# Voice_Interaction_Hat_for_MakePython_v2_.net
KiCad netlist of a schematic drawn in EAGLE
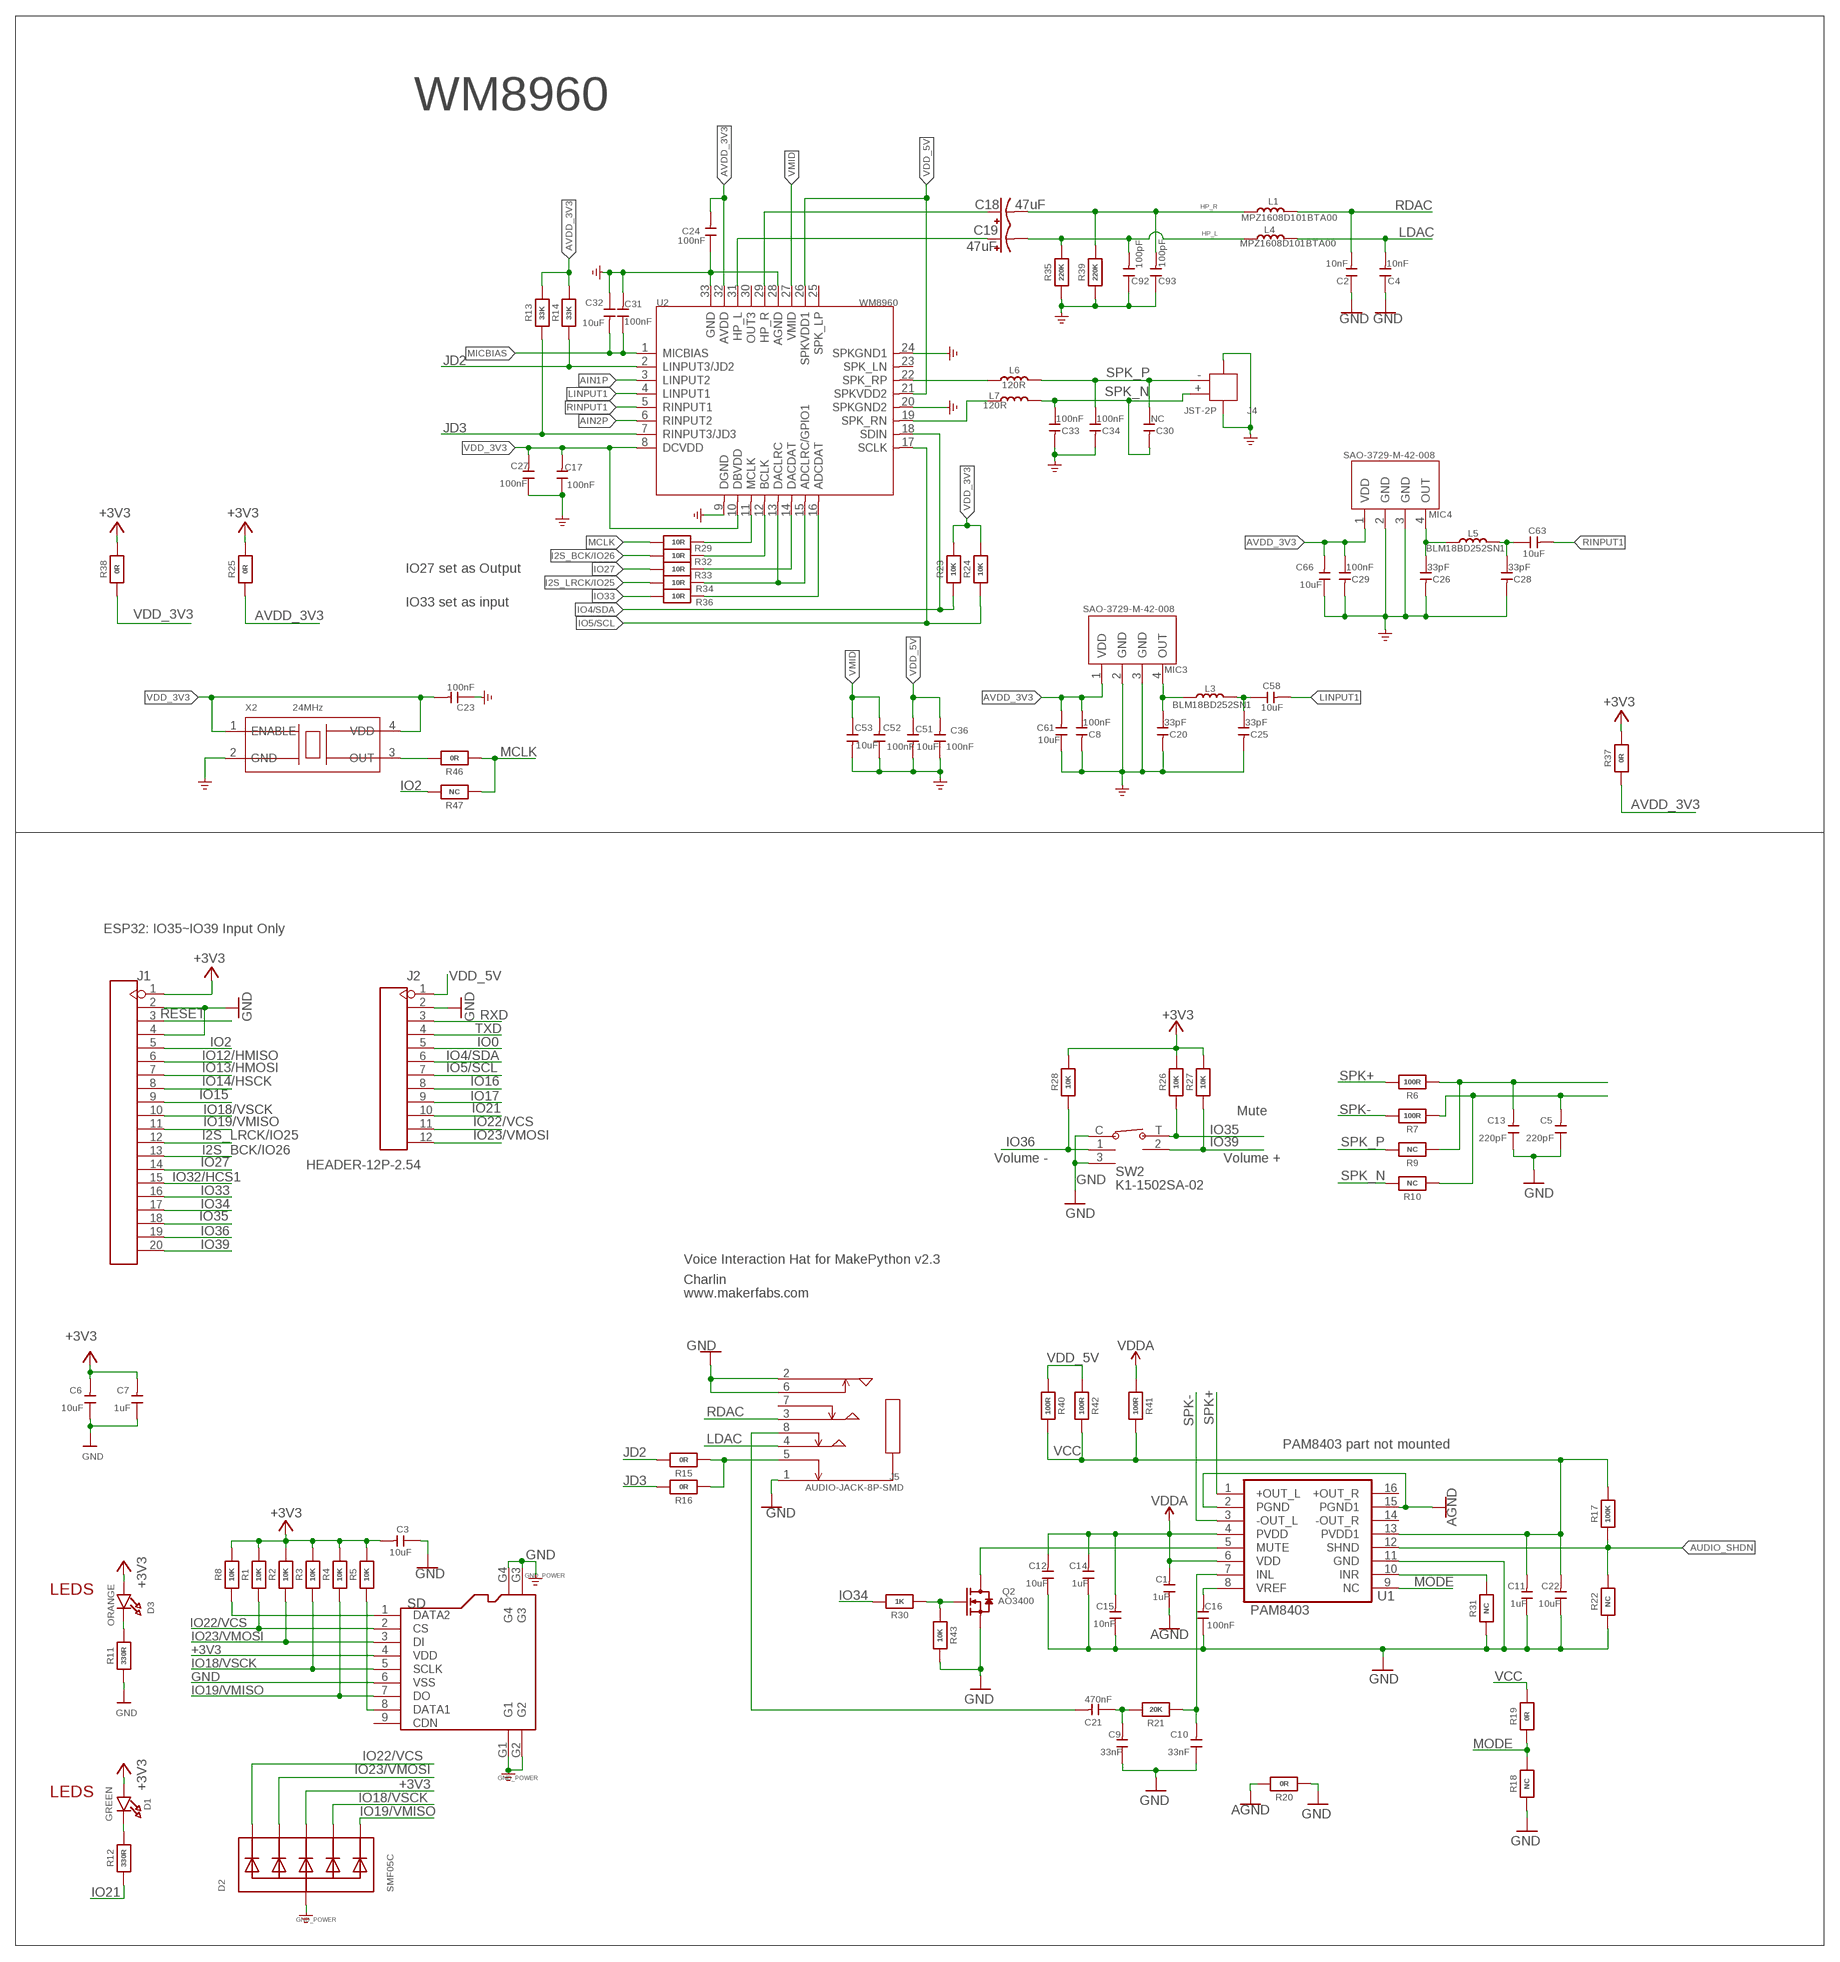
[diagram p0: schematic, sheet 1]

(export (version "E")
  (design (tool "Eeschema 10.0.6"))
  (components
    (comp (ref "C1")
      (value "1uF")
      (footprint "eagle-import:DISCRETE_C0603")
      (libsource (lib "eagle-import") (part "DISCRETE_C-0603"))
    )
    (comp (ref "C2")
      (value "10nF")
      (footprint "eagle-import:C0402")
      (libsource (lib "eagle-import") (part "CAP-0402"))
    )
    (comp (ref "C3")
      (value "10uF")
      (footprint "eagle-import:DISCRETE_C0603")
      (libsource (lib "eagle-import") (part "DISCRETE_C-0603"))
    )
    (comp (ref "C4")
      (value "10nF")
      (footprint "eagle-import:C0402")
      (libsource (lib "eagle-import") (part "CAP-0402"))
    )
    (comp (ref "C5")
      (value "220pF")
      (footprint "eagle-import:DISCRETE_C0603")
      (libsource (lib "eagle-import") (part "DISCRETE_C-0603"))
    )
    (comp (ref "C6")
      (value "10uF")
      (footprint "eagle-import:DISCRETE_C0603")
      (libsource (lib "eagle-import") (part "DISCRETE_C-0603"))
    )
    (comp (ref "C7")
      (value "1uF")
      (footprint "eagle-import:DISCRETE_C0603")
      (libsource (lib "eagle-import") (part "DISCRETE_C-0603"))
    )
    (comp (ref "C8")
      (value "100nF")
      (footprint "eagle-import:C0603")
      (libsource (lib "eagle-import") (part "CAP-0603"))
    )
    (comp (ref "C9")
      (value "33nF")
      (footprint "eagle-import:DISCRETE_C0603")
      (libsource (lib "eagle-import") (part "DISCRETE_C-0603"))
    )
    (comp (ref "C10")
      (value "33nF")
      (footprint "eagle-import:DISCRETE_C0603")
      (libsource (lib "eagle-import") (part "DISCRETE_C-0603"))
    )
    (comp (ref "C11")
      (value "1uF")
      (footprint "eagle-import:DISCRETE_C0603")
      (libsource (lib "eagle-import") (part "DISCRETE_C-0603"))
    )
    (comp (ref "C12")
      (value "10uF")
      (footprint "eagle-import:DISCRETE_C0603")
      (libsource (lib "eagle-import") (part "DISCRETE_C-0603"))
    )
    (comp (ref "C13")
      (value "220pF")
      (footprint "eagle-import:DISCRETE_C0603")
      (libsource (lib "eagle-import") (part "DISCRETE_C-0603"))
    )
    (comp (ref "C14")
      (value "1uF")
      (footprint "eagle-import:DISCRETE_C0603")
      (libsource (lib "eagle-import") (part "DISCRETE_C-0603"))
    )
    (comp (ref "C15")
      (value "10nF")
      (footprint "eagle-import:DISCRETE_C0603")
      (libsource (lib "eagle-import") (part "DISCRETE_C-0603"))
    )
    (comp (ref "C16")
      (value "100nF")
      (footprint "eagle-import:DISCRETE_C0603")
      (libsource (lib "eagle-import") (part "DISCRETE_C-0603"))
    )
    (comp (ref "C17")
      (value "100nF")
      (footprint "eagle-import:C0402")
      (libsource (lib "eagle-import") (part "CAP-0402"))
    )
    (comp (ref "C18")
      (value "47uF")
      (footprint "eagle-import:EIA3528")
      (libsource (lib "eagle-import") (part "47UF-POLAR-EIA3528-10V-10%"))
    )
    (comp (ref "C19")
      (value "47uF")
      (footprint "eagle-import:EIA3528")
      (libsource (lib "eagle-import") (part "47UF-POLAR-EIA3528-10V-10%"))
    )
    (comp (ref "C20")
      (value "33pF")
      (footprint "eagle-import:C0603")
      (libsource (lib "eagle-import") (part "CAP-0603"))
    )
    (comp (ref "C21")
      (value "470nF")
      (footprint "eagle-import:DISCRETE_C0603")
      (libsource (lib "eagle-import") (part "DISCRETE_C-0603"))
    )
    (comp (ref "C22")
      (value "10uF")
      (footprint "eagle-import:DISCRETE_C0603")
      (libsource (lib "eagle-import") (part "DISCRETE_C-0603"))
    )
    (comp (ref "C23")
      (value "100nF")
      (footprint "eagle-import:C0402")
      (libsource (lib "eagle-import") (part "CAP-0402"))
    )
    (comp (ref "C24")
      (value "100nF")
      (footprint "eagle-import:C0402")
      (libsource (lib "eagle-import") (part "CAP-0402"))
    )
    (comp (ref "C25")
      (value "33pF")
      (footprint "eagle-import:C0603")
      (libsource (lib "eagle-import") (part "CAP-0603"))
    )
    (comp (ref "C26")
      (value "33pF")
      (footprint "eagle-import:C0603")
      (libsource (lib "eagle-import") (part "CAP-0603"))
    )
    (comp (ref "C27")
      (value "100nF")
      (footprint "eagle-import:C0402")
      (libsource (lib "eagle-import") (part "CAP-0402"))
    )
    (comp (ref "C28")
      (value "33pF")
      (footprint "eagle-import:C0603")
      (libsource (lib "eagle-import") (part "CAP-0603"))
    )
    (comp (ref "C29")
      (value "100nF")
      (footprint "eagle-import:C0603")
      (libsource (lib "eagle-import") (part "CAP-0603"))
    )
    (comp (ref "C30")
      (value "NC")
      (footprint "eagle-import:C0603")
      (libsource (lib "eagle-import") (part "CAP-0603"))
    )
    (comp (ref "C31")
      (value "100nF")
      (footprint "eagle-import:C0402")
      (libsource (lib "eagle-import") (part "CAP-0402"))
    )
    (comp (ref "C32")
      (value "10uF")
      (footprint "eagle-import:C0603")
      (libsource (lib "eagle-import") (part "CAP-0603"))
    )
    (comp (ref "C33")
      (value "100nF")
      (footprint "eagle-import:C0603")
      (libsource (lib "eagle-import") (part "CAP-0603"))
    )
    (comp (ref "C34")
      (value "100nF")
      (footprint "eagle-import:C0603")
      (libsource (lib "eagle-import") (part "CAP-0603"))
    )
    (comp (ref "C36")
      (value "100nF")
      (footprint "eagle-import:C0402")
      (libsource (lib "eagle-import") (part "CAP-0402"))
    )
    (comp (ref "C51")
      (value "10uF")
      (footprint "eagle-import:C0603")
      (libsource (lib "eagle-import") (part "CAP-0603"))
    )
    (comp (ref "C52")
      (value "100nF")
      (footprint "eagle-import:C0402")
      (libsource (lib "eagle-import") (part "CAP-0402"))
    )
    (comp (ref "C53")
      (value "10uF")
      (footprint "eagle-import:C0603")
      (libsource (lib "eagle-import") (part "CAP-0603"))
    )
    (comp (ref "C58")
      (value "10uF")
      (footprint "eagle-import:C0603")
      (libsource (lib "eagle-import") (part "CAP-0603"))
    )
    (comp (ref "C61")
      (value "10uF")
      (footprint "eagle-import:C0603")
      (libsource (lib "eagle-import") (part "CAP-0603"))
    )
    (comp (ref "C63")
      (value "10uF")
      (footprint "eagle-import:C0603")
      (libsource (lib "eagle-import") (part "CAP-0603"))
    )
    (comp (ref "C66")
      (value "10uF")
      (footprint "eagle-import:C0603")
      (libsource (lib "eagle-import") (part "CAP-0603"))
    )
    (comp (ref "C92")
      (value "100pF")
      (footprint "eagle-import:C0402")
      (libsource (lib "eagle-import") (part "CAP-0402"))
    )
    (comp (ref "C93")
      (value "100pF")
      (footprint "eagle-import:C0402")
      (libsource (lib "eagle-import") (part "CAP-0402"))
    )
    (comp (ref "D1")
      (value "GREEN")
      (footprint "eagle-import:CHIPLED_0805_NOOUTLINE")
      (libsource (lib "eagle-import") (part "LED0805_NOOUTLINE"))
    )
    (comp (ref "D2")
      (value "SMF05C")
      (footprint "eagle-import:SOT363")
      (libsource (lib "eagle-import") (part "TVSARRAY_5LANE"))
    )
    (comp (ref "D3")
      (value "ORANGE")
      (footprint "eagle-import:CHIPLED_0805_NOOUTLINE")
      (libsource (lib "eagle-import") (part "LED0805_NOOUTLINE"))
    )
    (comp (ref "J1")
      (value "HEADER-20P-2.54")
      (footprint "eagle-import:20P-2.54")
      (libsource (lib "eagle-import") (part "HEADER-20P-2.54"))
    )
    (comp (ref "J2")
      (value "HEADER-12P-2.54")
      (footprint "eagle-import:12P-2.54")
      (libsource (lib "eagle-import") (part "HEADER-12P-2.54"))
    )
    (comp (ref "J4")
      (value "JST-2P")
      (footprint "eagle-import:HW2-SMD-2.0-90D")
      (libsource (lib "eagle-import") (part "JST-2P-SMD'2.0'"))
    )
    (comp (ref "J5")
      (value "AUDIO-JACK-8P-SMD")
      (footprint "eagle-import:AUDIO8P-SMD-3.5-14.5X6.1X4.0MM")
      (libsource (lib "eagle-import") (part "AUDIO-JACK-8P-SMD'PJ-393'"))
    )
    (comp (ref "L1")
      (value "MPZ1608D101BTA00")
      (footprint "eagle-import:L0603")
      (libsource (lib "eagle-import") (part "INDUCTOR/FERRITE-BEAD'0603'"))
    )
    (comp (ref "L3")
      (value "BLM18BD252SN1")
      (footprint "eagle-import:L0603")
      (libsource (lib "eagle-import") (part "INDUCTOR/FERRITE-BEAD'0603'"))
    )
    (comp (ref "L4")
      (value "MPZ1608D101BTA00")
      (footprint "eagle-import:L0603")
      (libsource (lib "eagle-import") (part "INDUCTOR/FERRITE-BEAD'0603'"))
    )
    (comp (ref "L5")
      (value "BLM18BD252SN1")
      (footprint "eagle-import:L0603")
      (libsource (lib "eagle-import") (part "INDUCTOR/FERRITE-BEAD'0603'"))
    )
    (comp (ref "L6")
      (value "120R")
      (footprint "eagle-import:L0603")
      (libsource (lib "eagle-import") (part "INDUCTOR/FERRITE-BEAD'0603'"))
    )
    (comp (ref "L7")
      (value "120R")
      (footprint "eagle-import:L0603")
      (libsource (lib "eagle-import") (part "INDUCTOR/FERRITE-BEAD'0603'"))
    )
    (comp (ref "MIC3")
      (value "SAO-3729-M-42-008")
      (footprint "eagle-import:MIC4-SMD-3.76X2.95MM")
      (libsource (lib "eagle-import") (part "MIC-MSM421A3729H8-C"))
    )
    (comp (ref "MIC4")
      (value "SAO-3729-M-42-008")
      (footprint "eagle-import:MIC4-SMD-3.76X2.95MM")
      (libsource (lib "eagle-import") (part "MIC-MSM421A3729H8-C"))
    )
    (comp (ref "Q2")
      (value "AO3400")
      (footprint "eagle-import:SOT23@1")
      (libsource (lib "eagle-import") (part "MOSFET-N'SOT23'"))
    )
    (comp (ref "R1")
      (value "10K")
      (footprint "eagle-import:0603-NO")
      (libsource (lib "eagle-import") (part "RESISTOR_0603_NOOUT"))
    )
    (comp (ref "R2")
      (value "10K")
      (footprint "eagle-import:0603-NO")
      (libsource (lib "eagle-import") (part "RESISTOR_0603_NOOUT"))
    )
    (comp (ref "R3")
      (value "10K")
      (footprint "eagle-import:0603-NO")
      (libsource (lib "eagle-import") (part "RESISTOR_0603_NOOUT"))
    )
    (comp (ref "R4")
      (value "10K")
      (footprint "eagle-import:0603-NO")
      (libsource (lib "eagle-import") (part "RESISTOR_0603_NOOUT"))
    )
    (comp (ref "R5")
      (value "10K")
      (footprint "eagle-import:0603-NO")
      (libsource (lib "eagle-import") (part "RESISTOR_0603_NOOUT"))
    )
    (comp (ref "R6")
      (value "100R")
      (footprint "eagle-import:0603-NO")
      (libsource (lib "eagle-import") (part "RESISTOR_0603_NOOUT"))
    )
    (comp (ref "R7")
      (value "100R")
      (footprint "eagle-import:0603-NO")
      (libsource (lib "eagle-import") (part "RESISTOR_0603_NOOUT"))
    )
    (comp (ref "R8")
      (value "10K")
      (footprint "eagle-import:0603-NO")
      (libsource (lib "eagle-import") (part "RESISTOR_0603_NOOUT"))
    )
    (comp (ref "R9")
      (value "NC")
      (footprint "eagle-import:0603-NO")
      (libsource (lib "eagle-import") (part "RESISTOR_0603_NOOUT"))
    )
    (comp (ref "R10")
      (value "NC")
      (footprint "eagle-import:0603-NO")
      (libsource (lib "eagle-import") (part "RESISTOR_0603_NOOUT"))
    )
    (comp (ref "R11")
      (value "330R")
      (footprint "eagle-import:0603-NO")
      (libsource (lib "eagle-import") (part "RESISTOR_0603_NOOUT"))
    )
    (comp (ref "R12")
      (value "330R")
      (footprint "eagle-import:0603-NO")
      (libsource (lib "eagle-import") (part "RESISTOR_0603_NOOUT"))
    )
    (comp (ref "R13")
      (value "33K")
      (footprint "eagle-import:0603-NO")
      (libsource (lib "eagle-import") (part "RESISTOR_0603_NOOUT"))
    )
    (comp (ref "R14")
      (value "33K")
      (footprint "eagle-import:0603-NO")
      (libsource (lib "eagle-import") (part "RESISTOR_0603_NOOUT"))
    )
    (comp (ref "R15")
      (value "0R")
      (footprint "eagle-import:0603-NO")
      (libsource (lib "eagle-import") (part "RESISTOR_0603_NOOUT"))
    )
    (comp (ref "R16")
      (value "0R")
      (footprint "eagle-import:0603-NO")
      (libsource (lib "eagle-import") (part "RESISTOR_0603_NOOUT"))
    )
    (comp (ref "R17")
      (value "100K")
      (footprint "eagle-import:0603-NO")
      (libsource (lib "eagle-import") (part "RESISTOR_0603_NOOUT"))
    )
    (comp (ref "R18")
      (value "NC")
      (footprint "eagle-import:0603-NO")
      (libsource (lib "eagle-import") (part "RESISTOR_0603_NOOUT"))
    )
    (comp (ref "R19")
      (value "0R")
      (footprint "eagle-import:0603-NO")
      (libsource (lib "eagle-import") (part "RESISTOR_0603_NOOUT"))
    )
    (comp (ref "R20")
      (value "0R")
      (footprint "eagle-import:0603-NO")
      (libsource (lib "eagle-import") (part "RESISTOR_0603_NOOUT"))
    )
    (comp (ref "R21")
      (value "20K")
      (footprint "eagle-import:0603-NO")
      (libsource (lib "eagle-import") (part "RESISTOR_0603_NOOUT"))
    )
    (comp (ref "R22")
      (value "NC")
      (footprint "eagle-import:0603-NO")
      (libsource (lib "eagle-import") (part "RESISTOR_0603_NOOUT"))
    )
    (comp (ref "R23")
      (value "10K")
      (footprint "eagle-import:0603-NO")
      (libsource (lib "eagle-import") (part "RESISTOR_0603_NOOUT"))
    )
    (comp (ref "R24")
      (value "10K")
      (footprint "eagle-import:0603-NO")
      (libsource (lib "eagle-import") (part "RESISTOR_0603_NOOUT"))
    )
    (comp (ref "R25")
      (value "0R")
      (footprint "eagle-import:0603-NO")
      (libsource (lib "eagle-import") (part "RESISTOR_0603_NOOUT"))
    )
    (comp (ref "R26")
      (value "10K")
      (footprint "eagle-import:0603-NO")
      (libsource (lib "eagle-import") (part "RESISTOR_0603_NOOUT"))
    )
    (comp (ref "R27")
      (value "10K")
      (footprint "eagle-import:0603-NO")
      (libsource (lib "eagle-import") (part "RESISTOR_0603_NOOUT"))
    )
    (comp (ref "R28")
      (value "10K")
      (footprint "eagle-import:0603-NO")
      (libsource (lib "eagle-import") (part "RESISTOR_0603_NOOUT"))
    )
    (comp (ref "R29")
      (value "10R")
      (footprint "eagle-import:0603-NO")
      (libsource (lib "eagle-import") (part "RESISTOR_0603_NOOUT"))
    )
    (comp (ref "R30")
      (value "1K")
      (footprint "eagle-import:0603-NO")
      (libsource (lib "eagle-import") (part "RESISTOR_0603_NOOUT"))
    )
    (comp (ref "R31")
      (value "NC")
      (footprint "eagle-import:0603-NO")
      (libsource (lib "eagle-import") (part "RESISTOR_0603_NOOUT"))
    )
    (comp (ref "R32")
      (value "10R")
      (footprint "eagle-import:0603-NO")
      (libsource (lib "eagle-import") (part "RESISTOR_0603_NOOUT"))
    )
    (comp (ref "R33")
      (value "10R")
      (footprint "eagle-import:0603-NO")
      (libsource (lib "eagle-import") (part "RESISTOR_0603_NOOUT"))
    )
    (comp (ref "R34")
      (value "10R")
      (footprint "eagle-import:0603-NO")
      (libsource (lib "eagle-import") (part "RESISTOR_0603_NOOUT"))
    )
    (comp (ref "R35")
      (value "220K")
      (footprint "eagle-import:0603-NO")
      (libsource (lib "eagle-import") (part "RESISTOR_0603_NOOUT"))
    )
    (comp (ref "R36")
      (value "10R")
      (footprint "eagle-import:0603-NO")
      (libsource (lib "eagle-import") (part "RESISTOR_0603_NOOUT"))
    )
    (comp (ref "R37")
      (value "0R")
      (footprint "eagle-import:0603-NO")
      (libsource (lib "eagle-import") (part "RESISTOR_0603_NOOUT"))
    )
    (comp (ref "R38")
      (value "0R")
      (footprint "eagle-import:0603-NO")
      (libsource (lib "eagle-import") (part "RESISTOR_0603_NOOUT"))
    )
    (comp (ref "R39")
      (value "220K")
      (footprint "eagle-import:0603-NO")
      (libsource (lib "eagle-import") (part "RESISTOR_0603_NOOUT"))
    )
    (comp (ref "R40")
      (value "100R")
      (footprint "eagle-import:0603-NO")
      (libsource (lib "eagle-import") (part "RESISTOR_0603_NOOUT"))
    )
    (comp (ref "R41")
      (value "100R")
      (footprint "eagle-import:0603-NO")
      (libsource (lib "eagle-import") (part "RESISTOR_0603_NOOUT"))
    )
    (comp (ref "R42")
      (value "100R")
      (footprint "eagle-import:0603-NO")
      (libsource (lib "eagle-import") (part "RESISTOR_0603_NOOUT"))
    )
    (comp (ref "R43")
      (value "10K")
      (footprint "eagle-import:0603-NO")
      (libsource (lib "eagle-import") (part "RESISTOR_0603_NOOUT"))
    )
    (comp (ref "R46")
      (value "0R")
      (footprint "eagle-import:0603-NO")
      (libsource (lib "eagle-import") (part "RESISTOR_0603_NOOUT"))
    )
    (comp (ref "R47")
      (value "NC")
      (footprint "eagle-import:0603-NO")
      (libsource (lib "eagle-import") (part "RESISTOR_0603_NOOUT"))
    )
    (comp (ref "SD")
      (value "HOLDER-MICROSD-9P")
      (footprint "eagle-import:9P-SMD-W_-RING")
      (libsource (lib "eagle-import") (part "HOLDER-MICROSD-9P"))
    )
    (comp (ref "SW2")
      (value "K1-1502SA-02")
      (footprint "eagle-import:SMD5-60P-1180L1170W")
      (libsource (lib "eagle-import") (part "K1-1502SA-02"))
    )
    (comp (ref "U1")
      (value "PAM8403")
      (footprint "eagle-import:SOP-16")
      (libsource (lib "eagle-import") (part "PAM8403"))
    )
    (comp (ref "U2")
      (value "WM8960")
      (footprint "eagle-import:QFN32G-0.5-5X5MM")
      (libsource (lib "eagle-import") (part "AMPLIFIER-WM8960"))
    )
    (comp (ref "X2")
      (value "24MHz")
      (footprint "eagle-import:OSC4-SMD-2.5X2.0X0.8MM")
      (libsource (lib "eagle-import") (part "CRYSTAL-OSCILLATOR2.52.0"))
    )
  )
  (nets
    (net (code "1") (name "+3V3") (class "Default")
      (node (ref "C3") (pin "2") (pinfunction "2_2") (pintype "passive"))
      (node (ref "C6") (pin "2") (pinfunction "2_2") (pintype "passive"))
      (node (ref "C7") (pin "2") (pinfunction "2_2") (pintype "passive"))
      (node (ref "D1") (pin "A") (pinfunction "A_A") (pintype "passive"))
      (node (ref "D2") (pin "4") (pinfunction "C3_4") (pintype "passive"))
      (node (ref "D3") (pin "A") (pinfunction "A_A") (pintype "passive"))
      (node (ref "J1") (pin "1") (pinfunction "P$1_1") (pintype "bidirectional"))
      (node (ref "R1") (pin "2") (pinfunction "2_2") (pintype "passive"))
      (node (ref "R2") (pin "2") (pinfunction "2_2") (pintype "passive"))
      (node (ref "R25") (pin "2") (pinfunction "2_2") (pintype "passive"))
      (node (ref "R26") (pin "2") (pinfunction "2_2") (pintype "passive"))
      (node (ref "R27") (pin "2") (pinfunction "2_2") (pintype "passive"))
      (node (ref "R28") (pin "2") (pinfunction "2_2") (pintype "passive"))
      (node (ref "R3") (pin "2") (pinfunction "2_2") (pintype "passive"))
      (node (ref "R37") (pin "2") (pinfunction "2_2") (pintype "passive"))
      (node (ref "R38") (pin "2") (pinfunction "2_2") (pintype "passive"))
      (node (ref "R4") (pin "2") (pinfunction "2_2") (pintype "passive"))
      (node (ref "R5") (pin "2") (pinfunction "2_2") (pintype "passive"))
      (node (ref "R8") (pin "2") (pinfunction "2_2") (pintype "passive"))
      (node (ref "SD") (pin "4") (pinfunction "VDD_4") (pintype "bidirectional"))
    )
    (net (code "2") (name "/HP_L") (class "Default")
      (node (ref "C19") (pin "C") (pinfunction "-_C") (pintype "passive"))
      (node (ref "C92") (pin "2") (pinfunction "2_2") (pintype "passive"))
      (node (ref "L4") (pin "1") (pinfunction "1_1") (pintype "passive"))
      (node (ref "R35") (pin "2") (pinfunction "2_2") (pintype "passive"))
    )
    (net (code "3") (name "/HP_R") (class "Default")
      (node (ref "C18") (pin "C") (pinfunction "-_C") (pintype "passive"))
      (node (ref "C93") (pin "2") (pinfunction "2_2") (pintype "passive"))
      (node (ref "L1") (pin "1") (pinfunction "1_1") (pintype "passive"))
      (node (ref "R39") (pin "2") (pinfunction "2_2") (pintype "passive"))
    )
    (net (code "4") (name "/IO0") (class "Default")
      (node (ref "J2") (pin "5") (pinfunction "5_5") (pintype "bidirectional"))
    )
    (net (code "5") (name "/IO2") (class "Default")
      (node (ref "J1") (pin "5") (pinfunction "P$5_5") (pintype "bidirectional"))
      (node (ref "R47") (pin "2") (pinfunction "2_2") (pintype "passive"))
    )
    (net (code "6") (name "/IO12{slash}HMISO") (class "Default")
      (node (ref "J1") (pin "6") (pinfunction "P$6_6") (pintype "bidirectional"))
    )
    (net (code "7") (name "/IO13{slash}HMOSI") (class "Default")
      (node (ref "J1") (pin "7") (pinfunction "P$7_7") (pintype "bidirectional"))
    )
    (net (code "8") (name "/IO14{slash}HSCK") (class "Default")
      (node (ref "J1") (pin "8") (pinfunction "P$8_8") (pintype "bidirectional"))
    )
    (net (code "9") (name "/IO15") (class "Default")
      (node (ref "J1") (pin "9") (pinfunction "P$9_9") (pintype "bidirectional"))
    )
    (net (code "10") (name "/IO16") (class "Default")
      (node (ref "J2") (pin "8") (pinfunction "8_8") (pintype "bidirectional"))
    )
    (net (code "11") (name "/IO17") (class "Default")
      (node (ref "J2") (pin "9") (pinfunction "9_9") (pintype "bidirectional"))
    )
    (net (code "12") (name "/IO18{slash}VSCK") (class "Default")
      (node (ref "D2") (pin "5") (pinfunction "C4_5") (pintype "passive"))
      (node (ref "J1") (pin "10") (pinfunction "P$10_10") (pintype "bidirectional"))
      (node (ref "R3") (pin "1") (pinfunction "1_1") (pintype "passive"))
      (node (ref "SD") (pin "5") (pinfunction "SCLK_5") (pintype "bidirectional"))
    )
    (net (code "13") (name "/IO19{slash}VMISO") (class "Default")
      (node (ref "D2") (pin "6") (pinfunction "C5_6") (pintype "passive"))
      (node (ref "J1") (pin "11") (pinfunction "P$11_11") (pintype "bidirectional"))
      (node (ref "R4") (pin "1") (pinfunction "1_1") (pintype "passive"))
      (node (ref "SD") (pin "7") (pinfunction "DO_7") (pintype "bidirectional"))
    )
    (net (code "14") (name "/IO21") (class "Default")
      (node (ref "J2") (pin "10") (pinfunction "10_10") (pintype "bidirectional"))
      (node (ref "R12") (pin "1") (pinfunction "1_1") (pintype "passive"))
    )
    (net (code "15") (name "/IO22{slash}VCS") (class "Default")
      (node (ref "D2") (pin "1") (pinfunction "C1_1") (pintype "passive"))
      (node (ref "J2") (pin "11") (pinfunction "11_11") (pintype "bidirectional"))
      (node (ref "R1") (pin "1") (pinfunction "1_1") (pintype "passive"))
      (node (ref "SD") (pin "2") (pinfunction "CS_2") (pintype "bidirectional"))
    )
    (net (code "16") (name "/IO23{slash}VMOSI") (class "Default")
      (node (ref "D2") (pin "3") (pinfunction "C2_3") (pintype "passive"))
      (node (ref "J2") (pin "12") (pinfunction "12_12") (pintype "bidirectional"))
      (node (ref "R2") (pin "1") (pinfunction "1_1") (pintype "passive"))
      (node (ref "SD") (pin "3") (pinfunction "DI_3") (pintype "bidirectional"))
    )
    (net (code "17") (name "/IO32{slash}HCS1") (class "Default")
      (node (ref "J1") (pin "15") (pinfunction "P$15_15") (pintype "bidirectional"))
    )
    (net (code "18") (name "/IO34") (class "Default")
      (node (ref "J1") (pin "17") (pinfunction "P$17_17") (pintype "bidirectional"))
      (node (ref "R30") (pin "2") (pinfunction "2_2") (pintype "passive"))
    )
    (net (code "19") (name "/IO35") (class "Default")
      (node (ref "J1") (pin "18") (pinfunction "P$18_18") (pintype "bidirectional"))
      (node (ref "R26") (pin "1") (pinfunction "1_1") (pintype "passive"))
      (node (ref "SW2") (pin "T") (pinfunction "T_T") (pintype "bidirectional"))
    )
    (net (code "20") (name "/IO36") (class "Default")
      (node (ref "J1") (pin "19") (pinfunction "P$19_19") (pintype "bidirectional"))
      (node (ref "R28") (pin "1") (pinfunction "1_1") (pintype "passive"))
      (node (ref "SW2") (pin "1") (pinfunction "1_1") (pintype "bidirectional"))
    )
    (net (code "21") (name "/IO39") (class "Default")
      (node (ref "J1") (pin "20") (pinfunction "P$20_20") (pintype "bidirectional"))
      (node (ref "R27") (pin "1") (pinfunction "1_1") (pintype "passive"))
      (node (ref "SW2") (pin "2") (pinfunction "2_2") (pintype "bidirectional"))
    )
    (net (code "22") (name "/JD2") (class "Default")
      (node (ref "R14") (pin "1") (pinfunction "1_1") (pintype "passive"))
      (node (ref "R15") (pin "2") (pinfunction "2_2") (pintype "passive"))
      (node (ref "U2") (pin "2") (pinfunction "LINPUT3/JD2_2") (pintype "bidirectional"))
    )
    (net (code "23") (name "/JD3") (class "Default")
      (node (ref "R13") (pin "1") (pinfunction "1_1") (pintype "passive"))
      (node (ref "R16") (pin "2") (pinfunction "2_2") (pintype "passive"))
      (node (ref "U2") (pin "7") (pinfunction "RINPUT3/JD3_7") (pintype "bidirectional"))
    )
    (net (code "24") (name "/LDAC") (class "Default")
      (node (ref "C4") (pin "2") (pinfunction "2_2") (pintype "passive"))
      (node (ref "J5") (pin "4") (pinfunction "4_4") (pintype "bidirectional"))
      (node (ref "L4") (pin "2") (pinfunction "2_2") (pintype "passive"))
    )
    (net (code "25") (name "/MODE") (class "Default")
      (node (ref "R18") (pin "2") (pinfunction "2_2") (pintype "passive"))
      (node (ref "R19") (pin "1") (pinfunction "1_1") (pintype "passive"))
      (node (ref "U1") (pin "9") (pinfunction "NC_9") (pintype "output"))
    )
    (net (code "26") (name "/RDAC") (class "Default")
      (node (ref "C2") (pin "2") (pinfunction "2_2") (pintype "passive"))
      (node (ref "J5") (pin "3") (pinfunction "3_3") (pintype "bidirectional"))
      (node (ref "L1") (pin "2") (pinfunction "2_2") (pintype "passive"))
    )
    (net (code "27") (name "/RESET") (class "Default")
      (node (ref "J1") (pin "3") (pinfunction "P$3_3") (pintype "bidirectional"))
    )
    (net (code "28") (name "/RXD") (class "Default")
      (node (ref "J2") (pin "3") (pinfunction "3_3") (pintype "bidirectional"))
    )
    (net (code "29") (name "/SPK+") (class "Default")
      (node (ref "R6") (pin "2") (pinfunction "2_2") (pintype "passive"))
      (node (ref "U1") (pin "1") (pinfunction "+OUT_L_1") (pintype "input"))
    )
    (net (code "30") (name "/SPK-") (class "Default")
      (node (ref "R7") (pin "2") (pinfunction "2_2") (pintype "passive"))
      (node (ref "U1") (pin "3") (pinfunction "-OUT_L_3") (pintype "input"))
    )
    (net (code "31") (name "/SPK_N") (class "Default")
      (node (ref "C30") (pin "2") (pinfunction "2_2") (pintype "passive"))
      (node (ref "C33") (pin "1") (pinfunction "1_1") (pintype "passive"))
      (node (ref "J4") (pin "+") (pinfunction "1_+") (pintype "bidirectional"))
      (node (ref "L7") (pin "2") (pinfunction "2_2") (pintype "passive"))
      (node (ref "R10") (pin "2") (pinfunction "2_2") (pintype "passive"))
    )
    (net (code "32") (name "/SPK_P") (class "Default")
      (node (ref "C30") (pin "1") (pinfunction "1_1") (pintype "passive"))
      (node (ref "C34") (pin "1") (pinfunction "1_1") (pintype "passive"))
      (node (ref "J4") (pin "-") (pinfunction "2_-") (pintype "bidirectional"))
      (node (ref "L6") (pin "2") (pinfunction "2_2") (pintype "passive"))
      (node (ref "R9") (pin "2") (pinfunction "2_2") (pintype "passive"))
    )
    (net (code "33") (name "/TXD") (class "Default")
      (node (ref "J2") (pin "4") (pinfunction "4_4") (pintype "bidirectional"))
    )
    (net (code "34") (name "/VCC") (class "Default")
      (node (ref "C11") (pin "2") (pinfunction "2_2") (pintype "passive"))
      (node (ref "C22") (pin "2") (pinfunction "2_2") (pintype "passive"))
      (node (ref "R17") (pin "2") (pinfunction "2_2") (pintype "passive"))
      (node (ref "R19") (pin "2") (pinfunction "2_2") (pintype "passive"))
      (node (ref "R40") (pin "2") (pinfunction "2_2") (pintype "passive"))
      (node (ref "R41") (pin "2") (pinfunction "2_2") (pintype "passive"))
      (node (ref "R42") (pin "2") (pinfunction "2_2") (pintype "passive"))
      (node (ref "U1") (pin "13") (pinfunction "PVDD1_13") (pintype "output"))
    )
    (net (code "35") (name "AGND") (class "Default")
      (node (ref "C1") (pin "1") (pinfunction "1_1") (pintype "passive"))
      (node (ref "R20") (pin "2") (pinfunction "2_2") (pintype "passive"))
      (node (ref "U1") (pin "15") (pinfunction "PGND1_15") (pintype "output"))
      (node (ref "U1") (pin "2") (pinfunction "PGND_2") (pintype "input"))
    )
    (net (code "36") (name "AIN1P") (class "Default")
      (node (ref "U2") (pin "3") (pinfunction "LINPUT2_3") (pintype "bidirectional"))
    )
    (net (code "37") (name "AIN2P") (class "Default")
      (node (ref "U2") (pin "6") (pinfunction "RINPUT2_6") (pintype "bidirectional"))
    )
    (net (code "38") (name "AUDIO_SHDN") (class "Default")
      (node (ref "R17") (pin "1") (pinfunction "1_1") (pintype "passive"))
      (node (ref "R22") (pin "2") (pinfunction "2_2") (pintype "passive"))
      (node (ref "U1") (pin "12") (pinfunction "SHND_12") (pintype "output"))
    )
    (net (code "39") (name "AVDD_3V3") (class "Default")
      (node (ref "C24") (pin "2") (pinfunction "2_2") (pintype "passive"))
      (node (ref "C29") (pin "1") (pinfunction "1_1") (pintype "passive"))
      (node (ref "C61") (pin "2") (pinfunction "2_2") (pintype "passive"))
      (node (ref "C66") (pin "2") (pinfunction "2_2") (pintype "passive"))
      (node (ref "C8") (pin "1") (pinfunction "1_1") (pintype "passive"))
      (node (ref "MIC3") (pin "1") (pinfunction "VDD_1") (pintype "bidirectional"))
      (node (ref "MIC4") (pin "1") (pinfunction "VDD_1") (pintype "bidirectional"))
      (node (ref "R13") (pin "2") (pinfunction "2_2") (pintype "passive"))
      (node (ref "R14") (pin "2") (pinfunction "2_2") (pintype "passive"))
      (node (ref "R25") (pin "1") (pinfunction "1_1") (pintype "passive"))
      (node (ref "R37") (pin "1") (pinfunction "1_1") (pintype "passive"))
      (node (ref "U2") (pin "32") (pinfunction "AVDD_32") (pintype "bidirectional"))
    )
    (net (code "40") (name "GND") (class "Default")
      (node (ref "C10") (pin "1") (pinfunction "1_1") (pintype "passive"))
      (node (ref "C11") (pin "1") (pinfunction "1_1") (pintype "passive"))
      (node (ref "C12") (pin "1") (pinfunction "1_1") (pintype "passive"))
      (node (ref "C13") (pin "1") (pinfunction "1_1") (pintype "passive"))
      (node (ref "C14") (pin "1") (pinfunction "1_1") (pintype "passive"))
      (node (ref "C15") (pin "1") (pinfunction "1_1") (pintype "passive"))
      (node (ref "C16") (pin "1") (pinfunction "1_1") (pintype "passive"))
      (node (ref "C17") (pin "1") (pinfunction "1_1") (pintype "passive"))
      (node (ref "C2") (pin "1") (pinfunction "1_1") (pintype "passive"))
      (node (ref "C20") (pin "2") (pinfunction "2_2") (pintype "passive"))
      (node (ref "C22") (pin "1") (pinfunction "1_1") (pintype "passive"))
      (node (ref "C23") (pin "1") (pinfunction "1_1") (pintype "passive"))
      (node (ref "C24") (pin "1") (pinfunction "1_1") (pintype "passive"))
      (node (ref "C25") (pin "2") (pinfunction "2_2") (pintype "passive"))
      (node (ref "C26") (pin "2") (pinfunction "2_2") (pintype "passive"))
      (node (ref "C27") (pin "1") (pinfunction "1_1") (pintype "passive"))
      (node (ref "C28") (pin "2") (pinfunction "2_2") (pintype "passive"))
      (node (ref "C29") (pin "2") (pinfunction "2_2") (pintype "passive"))
      (node (ref "C3") (pin "1") (pinfunction "1_1") (pintype "passive"))
      (node (ref "C31") (pin "2") (pinfunction "2_2") (pintype "passive"))
      (node (ref "C32") (pin "1") (pinfunction "1_1") (pintype "passive"))
      (node (ref "C33") (pin "2") (pinfunction "2_2") (pintype "passive"))
      (node (ref "C34") (pin "2") (pinfunction "2_2") (pintype "passive"))
      (node (ref "C36") (pin "1") (pinfunction "1_1") (pintype "passive"))
      (node (ref "C4") (pin "1") (pinfunction "1_1") (pintype "passive"))
      (node (ref "C5") (pin "1") (pinfunction "1_1") (pintype "passive"))
      (node (ref "C51") (pin "2") (pinfunction "2_2") (pintype "passive"))
      (node (ref "C52") (pin "1") (pinfunction "1_1") (pintype "passive"))
      (node (ref "C53") (pin "2") (pinfunction "2_2") (pintype "passive"))
      (node (ref "C6") (pin "1") (pinfunction "1_1") (pintype "passive"))
      (node (ref "C61") (pin "1") (pinfunction "1_1") (pintype "passive"))
      (node (ref "C66") (pin "1") (pinfunction "1_1") (pintype "passive"))
      (node (ref "C7") (pin "1") (pinfunction "1_1") (pintype "passive"))
      (node (ref "C8") (pin "2") (pinfunction "2_2") (pintype "passive"))
      (node (ref "C9") (pin "1") (pinfunction "1_1") (pintype "passive"))
      (node (ref "C92") (pin "1") (pinfunction "1_1") (pintype "passive"))
      (node (ref "C93") (pin "1") (pinfunction "1_1") (pintype "passive"))
      (node (ref "D2") (pin "2") (pinfunction "A_2") (pintype "passive"))
      (node (ref "J1") (pin "2") (pinfunction "P$2_2") (pintype "bidirectional"))
      (node (ref "J1") (pin "4") (pinfunction "P$4_4") (pintype "bidirectional"))
      (node (ref "J2") (pin "2") (pinfunction "2_2") (pintype "bidirectional"))
      (node (ref "J4") (pin "3") (pinfunction "3_3") (pintype "bidirectional"))
      (node (ref "J4") (pin "4") (pinfunction "4_4") (pintype "bidirectional"))
      (node (ref "J5") (pin "1") (pinfunction "1_1") (pintype "bidirectional"))
      (node (ref "J5") (pin "2") (pinfunction "2_2") (pintype "bidirectional"))
      (node (ref "J5") (pin "6") (pinfunction "6_6") (pintype "bidirectional"))
      (node (ref "MIC3") (pin "2") (pinfunction "GND_2") (pintype "bidirectional"))
      (node (ref "MIC3") (pin "3") (pinfunction "GND_3") (pintype "bidirectional"))
      (node (ref "MIC4") (pin "2") (pinfunction "GND_2") (pintype "bidirectional"))
      (node (ref "MIC4") (pin "3") (pinfunction "GND_3") (pintype "bidirectional"))
      (node (ref "Q2") (pin "2") (pinfunction "S_2") (pintype "passive"))
      (node (ref "R11") (pin "1") (pinfunction "1_1") (pintype "passive"))
      (node (ref "R18") (pin "1") (pinfunction "1_1") (pintype "passive"))
      (node (ref "R20") (pin "1") (pinfunction "1_1") (pintype "passive"))
      (node (ref "R22") (pin "1") (pinfunction "1_1") (pintype "passive"))
      (node (ref "R31") (pin "1") (pinfunction "1_1") (pintype "passive"))
      (node (ref "R35") (pin "1") (pinfunction "1_1") (pintype "passive"))
      (node (ref "R39") (pin "1") (pinfunction "1_1") (pintype "passive"))
      (node (ref "R43") (pin "2") (pinfunction "2_2") (pintype "passive"))
      (node (ref "SD") (pin "6") (pinfunction "VSS_6") (pintype "bidirectional"))
      (node (ref "SD") (pin "G1") (pinfunction "G1_G1") (pintype "bidirectional"))
      (node (ref "SD") (pin "G2") (pinfunction "G2_G2") (pintype "bidirectional"))
      (node (ref "SD") (pin "G3") (pinfunction "G3_G3") (pintype "bidirectional"))
      (node (ref "SD") (pin "G4") (pinfunction "G4_G4") (pintype "bidirectional"))
      (node (ref "SW2") (pin "3") (pinfunction "3_3") (pintype "bidirectional"))
      (node (ref "SW2") (pin "C") (pinfunction "C_C") (pintype "bidirectional"))
      (node (ref "U1") (pin "11") (pinfunction "GND_11") (pintype "output"))
      (node (ref "U2") (pin "20") (pinfunction "SPKGND2_20") (pintype "bidirectional"))
      (node (ref "U2") (pin "24") (pinfunction "SPKGND1_24") (pintype "bidirectional"))
      (node (ref "U2") (pin "28") (pinfunction "AGND_28") (pintype "bidirectional"))
      (node (ref "U2") (pin "33") (pinfunction "GND_33") (pintype "bidirectional"))
      (node (ref "U2") (pin "9") (pinfunction "DGND_9") (pintype "bidirectional"))
      (node (ref "X2") (pin "2") (pinfunction "GND_2") (pintype "bidirectional"))
    )
    (net (code "41") (name "I2S_BCK{slash}IO26") (class "Default")
      (node (ref "J1") (pin "13") (pinfunction "P$13_13") (pintype "bidirectional"))
      (node (ref "R32") (pin "2") (pinfunction "2_2") (pintype "passive"))
    )
    (net (code "42") (name "I2S_LRCK{slash}IO25") (class "Default")
      (node (ref "J1") (pin "12") (pinfunction "P$12_12") (pintype "bidirectional"))
      (node (ref "R34") (pin "2") (pinfunction "2_2") (pintype "passive"))
    )
    (net (code "43") (name "IO4{slash}SDA") (class "Default")
      (node (ref "J2") (pin "6") (pinfunction "6_6") (pintype "bidirectional"))
      (node (ref "R23") (pin "1") (pinfunction "1_1") (pintype "passive"))
      (node (ref "U2") (pin "18") (pinfunction "SDIN_18") (pintype "bidirectional"))
    )
    (net (code "44") (name "IO5{slash}SCL") (class "Default")
      (node (ref "J2") (pin "7") (pinfunction "7_7") (pintype "bidirectional"))
      (node (ref "R24") (pin "1") (pinfunction "1_1") (pintype "passive"))
      (node (ref "U2") (pin "17") (pinfunction "SCLK_17") (pintype "bidirectional"))
    )
    (net (code "45") (name "IO27") (class "Default")
      (node (ref "J1") (pin "14") (pinfunction "P$14_14") (pintype "bidirectional"))
      (node (ref "R33") (pin "2") (pinfunction "2_2") (pintype "passive"))
    )
    (net (code "46") (name "IO33") (class "Default")
      (node (ref "J1") (pin "16") (pinfunction "P$16_16") (pintype "bidirectional"))
      (node (ref "R36") (pin "2") (pinfunction "2_2") (pintype "passive"))
    )
    (net (code "47") (name "LINPUT1") (class "Default")
      (node (ref "C58") (pin "2") (pinfunction "2_2") (pintype "passive"))
      (node (ref "U2") (pin "4") (pinfunction "LINPUT1_4") (pintype "bidirectional"))
    )
    (net (code "48") (name "MCLK") (class "Default")
      (node (ref "R29") (pin "2") (pinfunction "2_2") (pintype "passive"))
      (node (ref "R46") (pin "1") (pinfunction "1_1") (pintype "passive"))
      (node (ref "R47") (pin "1") (pinfunction "1_1") (pintype "passive"))
    )
    (net (code "49") (name "MICBIAS") (class "Default")
      (node (ref "C31") (pin "1") (pinfunction "1_1") (pintype "passive"))
      (node (ref "C32") (pin "2") (pinfunction "2_2") (pintype "passive"))
      (node (ref "U2") (pin "1") (pinfunction "MICBIAS_1") (pintype "bidirectional"))
    )
    (net (code "50") (name "Net-(C5-Pad2)") (class "Default")
      (node (ref "C5") (pin "2") (pinfunction "2_2") (pintype "passive"))
      (node (ref "R10") (pin "1") (pinfunction "1_1") (pintype "passive"))
      (node (ref "R7") (pin "1") (pinfunction "1_1") (pintype "passive"))
    )
    (net (code "51") (name "Net-(C13-Pad2)") (class "Default")
      (node (ref "C13") (pin "2") (pinfunction "2_2") (pintype "passive"))
      (node (ref "R6") (pin "1") (pinfunction "1_1") (pintype "passive"))
      (node (ref "R9") (pin "1") (pinfunction "1_1") (pintype "passive"))
    )
    (net (code "52") (name "Net-(C18-+)") (class "Default")
      (node (ref "C18") (pin "A") (pinfunction "+_A") (pintype "passive"))
      (node (ref "U2") (pin "29") (pinfunction "HP_R_29") (pintype "bidirectional"))
    )
    (net (code "53") (name "Net-(C19-+)") (class "Default")
      (node (ref "C19") (pin "A") (pinfunction "+_A") (pintype "passive"))
      (node (ref "U2") (pin "31") (pinfunction "HP_L_31") (pintype "bidirectional"))
    )
    (net (code "54") (name "Net-(C21-Pad1)") (class "Default")
      (node (ref "C21") (pin "1") (pinfunction "1_1") (pintype "passive"))
      (node (ref "C9") (pin "2") (pinfunction "2_2") (pintype "passive"))
      (node (ref "R21") (pin "2") (pinfunction "2_2") (pintype "passive"))
    )
    (net (code "55") (name "Net-(C21-Pad2)") (class "Default")
      (node (ref "C21") (pin "2") (pinfunction "2_2") (pintype "passive"))
      (node (ref "J5") (pin "8") (pinfunction "8_8") (pintype "bidirectional"))
    )
    (net (code "56") (name "Net-(C25-Pad1)") (class "Default")
      (node (ref "C25") (pin "1") (pinfunction "1_1") (pintype "passive"))
      (node (ref "C58") (pin "1") (pinfunction "1_1") (pintype "passive"))
      (node (ref "L3") (pin "2") (pinfunction "2_2") (pintype "passive"))
    )
    (net (code "57") (name "Net-(C28-Pad1)") (class "Default")
      (node (ref "C28") (pin "1") (pinfunction "1_1") (pintype "passive"))
      (node (ref "C63") (pin "1") (pinfunction "1_1") (pintype "passive"))
      (node (ref "L5") (pin "2") (pinfunction "2_2") (pintype "passive"))
    )
    (net (code "58") (name "Net-(D1-PadC)") (class "Default")
      (node (ref "D1") (pin "C") (pinfunction "C_C") (pintype "passive"))
      (node (ref "R12") (pin "2") (pinfunction "2_2") (pintype "passive"))
    )
    (net (code "59") (name "Net-(D3-PadC)") (class "Default")
      (node (ref "D3") (pin "C") (pinfunction "C_C") (pintype "passive"))
      (node (ref "R11") (pin "2") (pinfunction "2_2") (pintype "passive"))
    )
    (net (code "60") (name "Net-(J5-Pad5)") (class "Default")
      (node (ref "J5") (pin "5") (pinfunction "5_5") (pintype "bidirectional"))
      (node (ref "R15") (pin "1") (pinfunction "1_1") (pintype "passive"))
      (node (ref "R16") (pin "1") (pinfunction "1_1") (pintype "passive"))
    )
    (net (code "61") (name "Net-(MIC3-OUT)") (class "Default")
      (node (ref "C20") (pin "1") (pinfunction "1_1") (pintype "passive"))
      (node (ref "L3") (pin "1") (pinfunction "1_1") (pintype "passive"))
      (node (ref "MIC3") (pin "4") (pinfunction "OUT_4") (pintype "bidirectional"))
    )
    (net (code "62") (name "Net-(MIC4-OUT)") (class "Default")
      (node (ref "C26") (pin "1") (pinfunction "1_1") (pintype "passive"))
      (node (ref "L5") (pin "1") (pinfunction "1_1") (pintype "passive"))
      (node (ref "MIC4") (pin "4") (pinfunction "OUT_4") (pintype "bidirectional"))
    )
    (net (code "63") (name "Net-(Q2-D)") (class "Default")
      (node (ref "Q2") (pin "3") (pinfunction "D_3") (pintype "passive"))
      (node (ref "U1") (pin "5") (pinfunction "MUTE_5") (pintype "input"))
    )
    (net (code "64") (name "Net-(Q2-G)") (class "Default")
      (node (ref "Q2") (pin "1") (pinfunction "G_1") (pintype "passive"))
      (node (ref "R30") (pin "1") (pinfunction "1_1") (pintype "passive"))
      (node (ref "R43") (pin "1") (pinfunction "1_1") (pintype "passive"))
    )
    (net (code "65") (name "Net-(SD-DATA1)") (class "Default")
      (node (ref "R5") (pin "1") (pinfunction "1_1") (pintype "passive"))
      (node (ref "SD") (pin "8") (pinfunction "DATA1_8") (pintype "bidirectional"))
    )
    (net (code "66") (name "Net-(SD-DATA2)") (class "Default")
      (node (ref "R8") (pin "1") (pinfunction "1_1") (pintype "passive"))
      (node (ref "SD") (pin "1") (pinfunction "DATA2_1") (pintype "bidirectional"))
    )
    (net (code "67") (name "Net-(U1-INL)") (class "Default")
      (node (ref "C10") (pin "2") (pinfunction "2_2") (pintype "passive"))
      (node (ref "R21") (pin "1") (pinfunction "1_1") (pintype "passive"))
      (node (ref "U1") (pin "7") (pinfunction "INL_7") (pintype "input"))
    )
    (net (code "68") (name "Net-(U1-INR)") (class "Default")
      (node (ref "R31") (pin "2") (pinfunction "2_2") (pintype "passive"))
      (node (ref "U1") (pin "10") (pinfunction "INR_10") (pintype "output"))
    )
    (net (code "69") (name "Net-(U1-VREF)") (class "Default")
      (node (ref "C16") (pin "2") (pinfunction "2_2") (pintype "passive"))
      (node (ref "U1") (pin "8") (pinfunction "VREF_8") (pintype "input"))
    )
    (net (code "70") (name "Net-(U2-ADCDAT)") (class "Default")
      (node (ref "R36") (pin "1") (pinfunction "1_1") (pintype "passive"))
      (node (ref "U2") (pin "16") (pinfunction "ADCDAT_16") (pintype "bidirectional"))
    )
    (net (code "71") (name "Net-(U2-ADCLRC{slash}GPIO1)") (class "Default")
      (node (ref "R34") (pin "1") (pinfunction "1_1") (pintype "passive"))
      (node (ref "U2") (pin "13") (pinfunction "DACLRC_13") (pintype "bidirectional"))
      (node (ref "U2") (pin "15") (pinfunction "ADCLRC/GPIO1_15") (pintype "bidirectional"))
    )
    (net (code "72") (name "Net-(U2-BCLK)") (class "Default")
      (node (ref "R32") (pin "1") (pinfunction "1_1") (pintype "passive"))
      (node (ref "U2") (pin "12") (pinfunction "BCLK_12") (pintype "bidirectional"))
    )
    (net (code "73") (name "Net-(U2-DACDAT)") (class "Default")
      (node (ref "R33") (pin "1") (pinfunction "1_1") (pintype "passive"))
      (node (ref "U2") (pin "14") (pinfunction "DACDAT_14") (pintype "bidirectional"))
    )
    (net (code "74") (name "Net-(U2-MCLK)") (class "Default")
      (node (ref "R29") (pin "1") (pinfunction "1_1") (pintype "passive"))
      (node (ref "U2") (pin "11") (pinfunction "MCLK_11") (pintype "bidirectional"))
    )
    (net (code "75") (name "Net-(U2-SPK_RN)") (class "Default")
      (node (ref "L7") (pin "1") (pinfunction "1_1") (pintype "passive"))
      (node (ref "U2") (pin "19") (pinfunction "SPK_RN_19") (pintype "bidirectional"))
    )
    (net (code "76") (name "Net-(U2-SPK_RP)") (class "Default")
      (node (ref "L6") (pin "1") (pinfunction "1_1") (pintype "passive"))
      (node (ref "U2") (pin "22") (pinfunction "SPK_RP_22") (pintype "bidirectional"))
    )
    (net (code "77") (name "Net-(X2-OUT)") (class "Default")
      (node (ref "R46") (pin "2") (pinfunction "2_2") (pintype "passive"))
      (node (ref "X2") (pin "3") (pinfunction "OUT_3") (pintype "bidirectional"))
    )
    (net (code "78") (name "RINPUT1") (class "Default")
      (node (ref "C63") (pin "2") (pinfunction "2_2") (pintype "passive"))
      (node (ref "U2") (pin "5") (pinfunction "RINPUT1_5") (pintype "bidirectional"))
    )
    (net (code "79") (name "VDDA") (class "Default")
      (node (ref "C1") (pin "2") (pinfunction "2_2") (pintype "passive"))
      (node (ref "C12") (pin "2") (pinfunction "2_2") (pintype "passive"))
      (node (ref "C14") (pin "2") (pinfunction "2_2") (pintype "passive"))
      (node (ref "C15") (pin "2") (pinfunction "2_2") (pintype "passive"))
      (node (ref "R41") (pin "1") (pinfunction "1_1") (pintype "passive"))
      (node (ref "U1") (pin "4") (pinfunction "PVDD_4") (pintype "input"))
      (node (ref "U1") (pin "6") (pinfunction "VDD_6") (pintype "input"))
    )
    (net (code "80") (name "VDD_3V3") (class "Default")
      (node (ref "C17") (pin "2") (pinfunction "2_2") (pintype "passive"))
      (node (ref "C23") (pin "2") (pinfunction "2_2") (pintype "passive"))
      (node (ref "C27") (pin "2") (pinfunction "2_2") (pintype "passive"))
      (node (ref "R23") (pin "2") (pinfunction "2_2") (pintype "passive"))
      (node (ref "R24") (pin "2") (pinfunction "2_2") (pintype "passive"))
      (node (ref "R38") (pin "1") (pinfunction "1_1") (pintype "passive"))
      (node (ref "U2") (pin "10") (pinfunction "DBVDD_10") (pintype "bidirectional"))
      (node (ref "U2") (pin "8") (pinfunction "DCVDD_8") (pintype "bidirectional"))
      (node (ref "X2") (pin "1") (pinfunction "ENABLE_1") (pintype "bidirectional"))
      (node (ref "X2") (pin "4") (pinfunction "VDD_4") (pintype "bidirectional"))
    )
    (net (code "81") (name "VDD_5V") (class "Default")
      (node (ref "C36") (pin "2") (pinfunction "2_2") (pintype "passive"))
      (node (ref "C51") (pin "1") (pinfunction "1_1") (pintype "passive"))
      (node (ref "J2") (pin "1") (pinfunction "1_1") (pintype "bidirectional"))
      (node (ref "R40") (pin "1") (pinfunction "1_1") (pintype "passive"))
      (node (ref "R42") (pin "1") (pinfunction "1_1") (pintype "passive"))
      (node (ref "U2") (pin "21") (pinfunction "SPKVDD2_21") (pintype "bidirectional"))
      (node (ref "U2") (pin "26") (pinfunction "SPKVDD1_26") (pintype "bidirectional"))
    )
    (net (code "82") (name "VMID") (class "Default")
      (node (ref "C52") (pin "2") (pinfunction "2_2") (pintype "passive"))
      (node (ref "C53") (pin "1") (pinfunction "1_1") (pintype "passive"))
      (node (ref "U2") (pin "27") (pinfunction "VMID_27") (pintype "bidirectional"))
    )
    (net (code "83") (name "unconnected-(J5-Pad7)") (class "Default")
      (node (ref "J5") (pin "7") (pinfunction "7_7") (pintype "bidirectional"))
    )
    (net (code "84") (name "unconnected-(SD-CDN-Pad9)") (class "Default")
      (node (ref "SD") (pin "9") (pinfunction "CDN_9") (pintype "bidirectional"))
    )
    (net (code "85") (name "unconnected-(U1-+OUT_R-Pad16)") (class "Default")
      (node (ref "U1") (pin "16") (pinfunction "+OUT_R_16") (pintype "output"))
    )
    (net (code "86") (name "unconnected-(U1--OUT_R-Pad14)") (class "Default")
      (node (ref "U1") (pin "14") (pinfunction "-OUT_R_14") (pintype "output"))
    )
    (net (code "87") (name "unconnected-(U2-OUT3-Pad30)") (class "Default")
      (node (ref "U2") (pin "30") (pinfunction "OUT3_30") (pintype "bidirectional"))
    )
    (net (code "88") (name "unconnected-(U2-SPK_LN-Pad23)") (class "Default")
      (node (ref "U2") (pin "23") (pinfunction "SPK_LN_23") (pintype "bidirectional"))
    )
    (net (code "89") (name "unconnected-(U2-SPK_LP-Pad25)") (class "Default")
      (node (ref "U2") (pin "25") (pinfunction "SPK_LP_25") (pintype "bidirectional"))
    )
  )
)
